# FPGA.net
KiCad netlist of a schematic drawn in Altium Designer
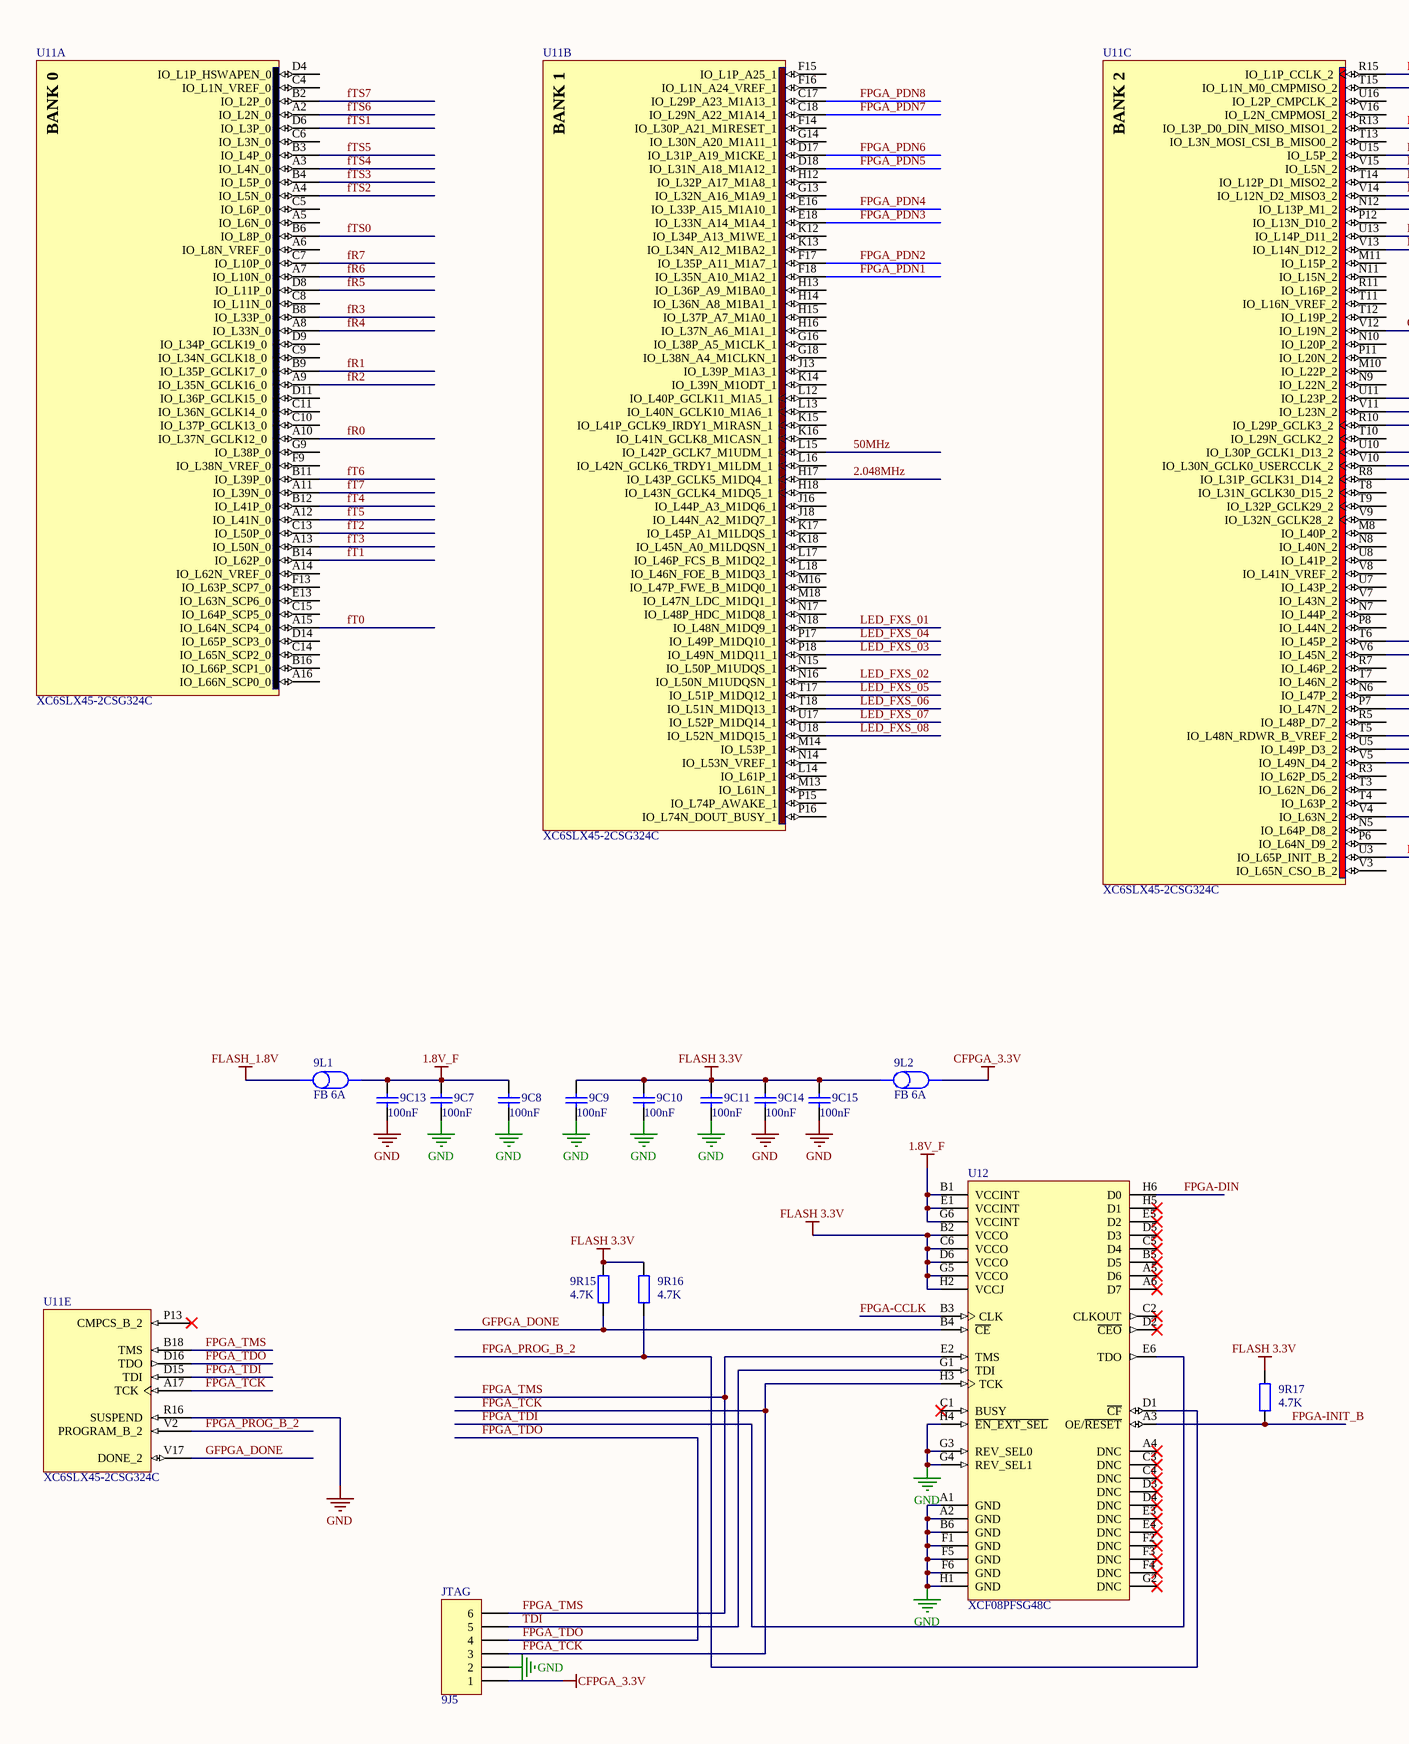
[diagram p0: FPGA.SchDoc, left]
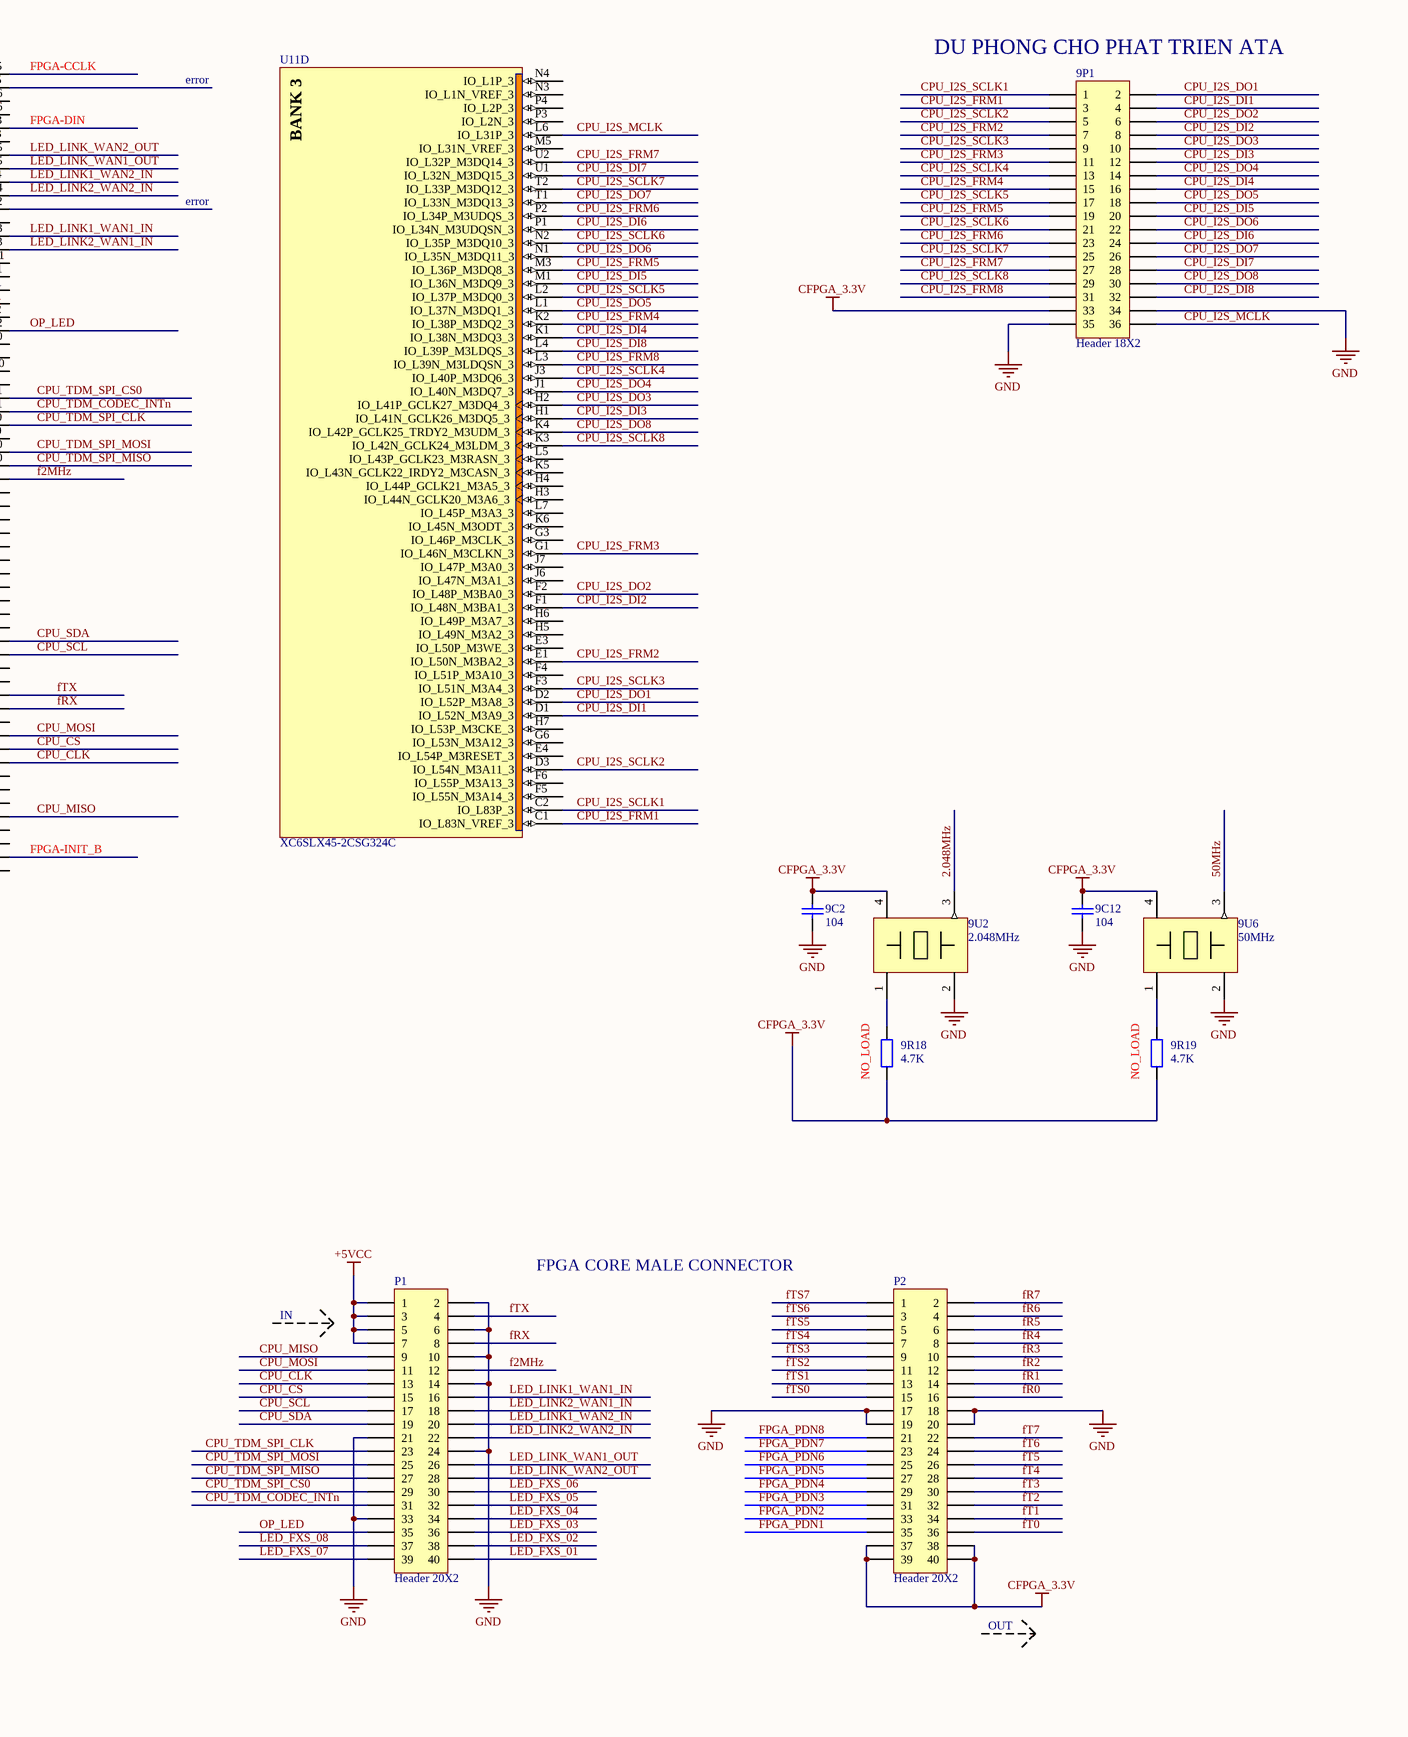
[diagram p1: FPGA.SchDoc, right]

(export (version "E")
  (design (tool "Eeschema 10.0.6"))
  (components
    (comp (ref "9C2")
      (value "CAP1")
      (footprint "0805C")
      (fields (field (name "CAP") "104"))
      (libsource (lib "BANGGOC") (part "CAP1"))
    )
    (comp (ref "9C7")
      (value "100nF")
      (footprint "C0402")
      (description "CAP CER 10V 10% 0402")
      (libsource (lib "my_lib") (part "CAP"))
    )
    (comp (ref "9C8")
      (value "100nF")
      (footprint "C0402")
      (description "CAP CER 10V 10% 0402")
      (libsource (lib "my_lib") (part "CAP"))
    )
    (comp (ref "9C9")
      (value "100nF")
      (footprint "C0402")
      (description "CAP CER 10V 10% 0402")
      (libsource (lib "my_lib") (part "CAP"))
    )
    (comp (ref "9C10")
      (value "100nF")
      (footprint "C0402")
      (description "CAP CER 10V 10% 0402")
      (libsource (lib "my_lib") (part "CAP"))
    )
    (comp (ref "9C11")
      (value "100nF")
      (footprint "C0402")
      (description "CAP CER 10V 10% 0402")
      (libsource (lib "my_lib") (part "CAP"))
    )
    (comp (ref "9C12")
      (value "CAP1")
      (footprint "0805C")
      (fields (field (name "CAP") "104"))
      (libsource (lib "BANGGOC") (part "CAP1"))
    )
    (comp (ref "9C13")
      (value "100nF")
      (footprint "C0402")
      (description "CAP CER 10V 10% 0402")
      (libsource (lib "my_lib") (part "CAP"))
    )
    (comp (ref "9C14")
      (value "100nF")
      (footprint "C0402")
      (description "CAP CER 10V 10% 0402")
      (libsource (lib "my_lib") (part "CAP"))
    )
    (comp (ref "9C15")
      (value "100nF")
      (footprint "C0402")
      (description "CAP CER 10V 10% 0402")
      (libsource (lib "my_lib") (part "CAP"))
    )
    (comp (ref "9J5")
      (value "JTAG")
      (footprint "HDR 1X6")
      (description "CONNECTOR HEADER 1x6 PITCH 2.54")
      (libsource (lib "my_lib") (part "J6x1"))
    )
    (comp (ref "9L1")
      (value "FB 6A")
      (footprint "0805")
      (description "FERRITE BEAD 22 OHM 0805 1LN")
      (fields (field (name "PART_NUMBER") "BLM21PG220SN1D"))
      (libsource (lib "HONG") (part "FB"))
    )
    (comp (ref "9L2")
      (value "FB 6A")
      (footprint "0805")
      (description "FERRITE BEAD 22 OHM 0805 1LN")
      (fields (field (name "PART_NUMBER") "BLM21PG220SN1D"))
      (libsource (lib "HONG") (part "FB"))
    )
    (comp (ref "9P1")
      (value "Header 18X2")
      (footprint "HDR2X18")
      (description "Header, 18-Pin, Dual row")
      (fields (field (name "PUBLISHER") "Altium Limited"))
      (libsource (lib "Miscellaneous Connectors") (part "Header 18X2"))
    )
    (comp (ref "9R15")
      (value "4.7K")
      (footprint "0603_1")
      (description "RES 1/8W 5% 0603")
      (libsource (lib "my_lib") (part "RES"))
    )
    (comp (ref "9R16")
      (value "4.7K")
      (footprint "0603_1")
      (description "RES 1/8W 5% 0603")
      (libsource (lib "my_lib") (part "RES"))
    )
    (comp (ref "9R17")
      (value "4.7K")
      (footprint "0603_1")
      (description "RES 1/8W 5% 0603")
      (libsource (lib "my_lib") (part "RES"))
    )
    (comp (ref "9R18")
      (value "4.7K")
      (footprint "0603_1")
      (description "RES 1/8W 5% 0603")
      (fields (field (name "LOAD") "NO_LOAD"))
      (libsource (lib "my_lib") (part "RES"))
    )
    (comp (ref "9R19")
      (value "4.7K")
      (footprint "0603_1")
      (description "RES 1/8W 5% 0603")
      (fields (field (name "LOAD") "NO_LOAD"))
      (libsource (lib "my_lib") (part "RES"))
    )
    (comp (ref "9U2")
      (value "2.048MHz")
      (footprint "CB3LV-3I-2M0480")
      (libsource (lib "BANGGOC") (part "CRYSTAL2"))
    )
    (comp (ref "9U6")
      (value "50MHz")
      (footprint "CB3LV-3I-2M0480")
      (libsource (lib "BANGGOC") (part "CRYSTAL2"))
    )
    (comp (ref "P1")
      (value "Header 20X2")
      (footprint "HEADER 40P MALE")
      (description "Header, 20-Pin, Dual row")
      (fields (field (name "PUBLISHER") "Altium Limited"))
      (libsource (lib "Miscellaneous Connectors") (part "Header 20X2"))
    )
    (comp (ref "P2")
      (value "Header 20X2")
      (footprint "HEADER 40P MALE")
      (description "Header, 20-Pin, Dual row")
      (fields (field (name "PUBLISHER") "Altium Limited"))
      (libsource (lib "Miscellaneous Connectors") (part "Header 20X2"))
    )
    (comp (ref "U11")
      (value "XC6SLX45-2CSG324C")
      (footprint "CSG324")
      (fields (field (name "PUBLISHER") "Altium Limited"))
      (libsource (lib "") (part "XC6SLX45-2CSG324C_1"))
    )
    (comp (ref "U12")
      (value "XCF08PFSG48C")
      (footprint "XCF08PFSG48C")
      (fields (field (name "PUBLISHER") "Altium Limited"))
      (libsource (lib "my_lib") (part "XCF08PFSG48C"))
    )
  )
  (nets
    (net (code "1") (name "+5VCC") (class "Default")
      (node (ref "P1") (pin "1") (pinfunction "1_1") (pintype "passive"))
      (node (ref "P1") (pin "3") (pinfunction "3_3") (pintype "passive"))
      (node (ref "P1") (pin "5") (pinfunction "5_5") (pintype "passive"))
      (node (ref "P1") (pin "7") (pinfunction "7_7") (pintype "passive"))
    )
    (net (code "2") (name "/2.048MHz") (class "Default")
      (node (ref "9U2") (pin "3") (pinfunction "3_3") (pintype "output"))
      (node (ref "U11") (pin "H17") (pinfunction "IO_L43P_GCLK5_M1DQ4_1_H17") (pintype "bidirectional"))
    )
    (net (code "3") (name "/50MHz") (class "Default")
      (node (ref "9U6") (pin "3") (pinfunction "3_3") (pintype "output"))
      (node (ref "U11") (pin "L15") (pinfunction "IO_L42P_GCLK7_M1UDM_1_L15") (pintype "bidirectional"))
    )
    (net (code "4") (name "/CPU_CLK") (class "Default")
      (node (ref "P1") (pin "13") (pinfunction "13_13") (pintype "passive"))
      (node (ref "U11") (pin "V5") (pinfunction "IO_L49N_D4_2_V5") (pintype "bidirectional"))
    )
    (net (code "5") (name "/CPU_CS") (class "Default")
      (node (ref "P1") (pin "15") (pinfunction "15_15") (pintype "passive"))
      (node (ref "U11") (pin "U5") (pinfunction "IO_L49P_D3_2_U5") (pintype "bidirectional"))
    )
    (net (code "6") (name "/CPU_I2S_DI1") (class "Default")
      (node (ref "9P1") (pin "4") (pinfunction "4_4") (pintype "passive"))
      (node (ref "U11") (pin "D1") (pinfunction "IO_L52N_M3A9_3_D1") (pintype "bidirectional"))
    )
    (net (code "7") (name "/CPU_I2S_DI2") (class "Default")
      (node (ref "9P1") (pin "8") (pinfunction "8_8") (pintype "passive"))
      (node (ref "U11") (pin "F1") (pinfunction "IO_L48N_M3BA1_3_F1") (pintype "bidirectional"))
    )
    (net (code "8") (name "/CPU_I2S_DI3") (class "Default")
      (node (ref "9P1") (pin "12") (pinfunction "12_12") (pintype "passive"))
      (node (ref "U11") (pin "H1") (pinfunction "IO_L41N_GCLK26_M3DQ5_3_H1") (pintype "bidirectional"))
    )
    (net (code "9") (name "/CPU_I2S_DI4") (class "Default")
      (node (ref "9P1") (pin "16") (pinfunction "16_16") (pintype "passive"))
      (node (ref "U11") (pin "K1") (pinfunction "IO_L38N_M3DQ3_3_K1") (pintype "bidirectional"))
    )
    (net (code "10") (name "/CPU_I2S_DI5") (class "Default")
      (node (ref "9P1") (pin "20") (pinfunction "20_20") (pintype "passive"))
      (node (ref "U11") (pin "M1") (pinfunction "IO_L36N_M3DQ9_3_M1") (pintype "bidirectional"))
    )
    (net (code "11") (name "/CPU_I2S_DI6") (class "Default")
      (node (ref "9P1") (pin "24") (pinfunction "24_24") (pintype "passive"))
      (node (ref "U11") (pin "P1") (pinfunction "IO_L34N_M3UDQSN_3_P1") (pintype "bidirectional"))
    )
    (net (code "12") (name "/CPU_I2S_DI7") (class "Default")
      (node (ref "9P1") (pin "28") (pinfunction "28_28") (pintype "passive"))
      (node (ref "U11") (pin "U1") (pinfunction "IO_L32N_M3DQ15_3_U1") (pintype "bidirectional"))
    )
    (net (code "13") (name "/CPU_I2S_DI8") (class "Default")
      (node (ref "9P1") (pin "32") (pinfunction "32_32") (pintype "passive"))
      (node (ref "U11") (pin "L4") (pinfunction "IO_L39P_M3LDQS_3_L4") (pintype "bidirectional"))
    )
    (net (code "14") (name "/CPU_I2S_DO1") (class "Default")
      (node (ref "9P1") (pin "2") (pinfunction "2_2") (pintype "passive"))
      (node (ref "U11") (pin "D2") (pinfunction "IO_L52P_M3A8_3_D2") (pintype "bidirectional"))
    )
    (net (code "15") (name "/CPU_I2S_DO2") (class "Default")
      (node (ref "9P1") (pin "6") (pinfunction "6_6") (pintype "passive"))
      (node (ref "U11") (pin "F2") (pinfunction "IO_L48P_M3BA0_3_F2") (pintype "bidirectional"))
    )
    (net (code "16") (name "/CPU_I2S_DO3") (class "Default")
      (node (ref "9P1") (pin "10") (pinfunction "10_10") (pintype "passive"))
      (node (ref "U11") (pin "H2") (pinfunction "IO_L41P_GCLK27_M3DQ4_3_H2") (pintype "bidirectional"))
    )
    (net (code "17") (name "/CPU_I2S_DO4") (class "Default")
      (node (ref "9P1") (pin "14") (pinfunction "14_14") (pintype "passive"))
      (node (ref "U11") (pin "J1") (pinfunction "IO_L40N_M3DQ7_3_J1") (pintype "bidirectional"))
    )
    (net (code "18") (name "/CPU_I2S_DO5") (class "Default")
      (node (ref "9P1") (pin "18") (pinfunction "18_18") (pintype "passive"))
      (node (ref "U11") (pin "L1") (pinfunction "IO_L37N_M3DQ1_3_L1") (pintype "bidirectional"))
    )
    (net (code "19") (name "/CPU_I2S_DO6") (class "Default")
      (node (ref "9P1") (pin "22") (pinfunction "22_22") (pintype "passive"))
      (node (ref "U11") (pin "N1") (pinfunction "IO_L35N_M3DQ11_3_N1") (pintype "bidirectional"))
    )
    (net (code "20") (name "/CPU_I2S_DO7") (class "Default")
      (node (ref "9P1") (pin "26") (pinfunction "26_26") (pintype "passive"))
      (node (ref "U11") (pin "T1") (pinfunction "IO_L33N_M3DQ13_3_T1") (pintype "bidirectional"))
    )
    (net (code "21") (name "/CPU_I2S_DO8") (class "Default")
      (node (ref "9P1") (pin "30") (pinfunction "30_30") (pintype "passive"))
      (node (ref "U11") (pin "K4") (pinfunction "IO_L42P_GCLK25_TRDY2_M3UDM_3_K4") (pintype "bidirectional"))
    )
    (net (code "22") (name "/CPU_I2S_FRM1") (class "Default")
      (node (ref "9P1") (pin "3") (pinfunction "3_3") (pintype "passive"))
      (node (ref "U11") (pin "C1") (pinfunction "IO_L83N_VREF_3_C1") (pintype "bidirectional"))
    )
    (net (code "23") (name "/CPU_I2S_FRM2") (class "Default")
      (node (ref "9P1") (pin "7") (pinfunction "7_7") (pintype "passive"))
      (node (ref "U11") (pin "E1") (pinfunction "IO_L50N_M3BA2_3_E1") (pintype "bidirectional"))
    )
    (net (code "24") (name "/CPU_I2S_FRM3") (class "Default")
      (node (ref "9P1") (pin "11") (pinfunction "11_11") (pintype "passive"))
      (node (ref "U11") (pin "G1") (pinfunction "IO_L46N_M3CLKN_3_G1") (pintype "bidirectional"))
    )
    (net (code "25") (name "/CPU_I2S_FRM4") (class "Default")
      (node (ref "9P1") (pin "15") (pinfunction "15_15") (pintype "passive"))
      (node (ref "U11") (pin "K2") (pinfunction "IO_L38P_M3DQ2_3_K2") (pintype "bidirectional"))
    )
    (net (code "26") (name "/CPU_I2S_FRM5") (class "Default")
      (node (ref "9P1") (pin "19") (pinfunction "19_19") (pintype "passive"))
      (node (ref "U11") (pin "M3") (pinfunction "IO_L36P_M3DQ8_3_M3") (pintype "bidirectional"))
    )
    (net (code "27") (name "/CPU_I2S_FRM6") (class "Default")
      (node (ref "9P1") (pin "23") (pinfunction "23_23") (pintype "passive"))
      (node (ref "U11") (pin "P2") (pinfunction "IO_L34P_M3UDQS_3_P2") (pintype "bidirectional"))
    )
    (net (code "28") (name "/CPU_I2S_FRM7") (class "Default")
      (node (ref "9P1") (pin "27") (pinfunction "27_27") (pintype "passive"))
      (node (ref "U11") (pin "U2") (pinfunction "IO_L32P_M3DQ14_3_U2") (pintype "bidirectional"))
    )
    (net (code "29") (name "/CPU_I2S_FRM8") (class "Default")
      (node (ref "9P1") (pin "31") (pinfunction "31_31") (pintype "passive"))
      (node (ref "U11") (pin "L3") (pinfunction "IO_L39N_M3LDQSN_3_L3") (pintype "bidirectional"))
    )
    (net (code "30") (name "/CPU_I2S_MCLK") (class "Default")
      (node (ref "9P1") (pin "36") (pinfunction "36_36") (pintype "passive"))
      (node (ref "U11") (pin "L6") (pinfunction "IO_L31P_3_L6") (pintype "bidirectional"))
    )
    (net (code "31") (name "/CPU_I2S_SCLK1") (class "Default")
      (node (ref "9P1") (pin "1") (pinfunction "1_1") (pintype "passive"))
      (node (ref "U11") (pin "C2") (pinfunction "IO_L83P_3_C2") (pintype "bidirectional"))
    )
    (net (code "32") (name "/CPU_I2S_SCLK2") (class "Default")
      (node (ref "9P1") (pin "5") (pinfunction "5_5") (pintype "passive"))
      (node (ref "U11") (pin "D3") (pinfunction "IO_L54N_M3A11_3_D3") (pintype "bidirectional"))
    )
    (net (code "33") (name "/CPU_I2S_SCLK3") (class "Default")
      (node (ref "9P1") (pin "9") (pinfunction "9_9") (pintype "passive"))
      (node (ref "U11") (pin "F3") (pinfunction "IO_L51N_M3A4_3_F3") (pintype "bidirectional"))
    )
    (net (code "34") (name "/CPU_I2S_SCLK4") (class "Default")
      (node (ref "9P1") (pin "13") (pinfunction "13_13") (pintype "passive"))
      (node (ref "U11") (pin "J3") (pinfunction "IO_L40P_M3DQ6_3_J3") (pintype "bidirectional"))
    )
    (net (code "35") (name "/CPU_I2S_SCLK5") (class "Default")
      (node (ref "9P1") (pin "17") (pinfunction "17_17") (pintype "passive"))
      (node (ref "U11") (pin "L2") (pinfunction "IO_L37P_M3DQ0_3_L2") (pintype "bidirectional"))
    )
    (net (code "36") (name "/CPU_I2S_SCLK6") (class "Default")
      (node (ref "9P1") (pin "21") (pinfunction "21_21") (pintype "passive"))
      (node (ref "U11") (pin "N2") (pinfunction "IO_L35P_M3DQ10_3_N2") (pintype "bidirectional"))
    )
    (net (code "37") (name "/CPU_I2S_SCLK7") (class "Default")
      (node (ref "9P1") (pin "25") (pinfunction "25_25") (pintype "passive"))
      (node (ref "U11") (pin "T2") (pinfunction "IO_L33P_M3DQ12_3_T2") (pintype "bidirectional"))
    )
    (net (code "38") (name "/CPU_I2S_SCLK8") (class "Default")
      (node (ref "9P1") (pin "29") (pinfunction "29_29") (pintype "passive"))
      (node (ref "U11") (pin "K3") (pinfunction "IO_L42N_GCLK24_M3LDM_3_K3") (pintype "bidirectional"))
    )
    (net (code "39") (name "/CPU_MISO") (class "Default")
      (node (ref "P1") (pin "9") (pinfunction "9_9") (pintype "passive"))
      (node (ref "U11") (pin "V4") (pinfunction "IO_L63N_2_V4") (pintype "bidirectional"))
    )
    (net (code "40") (name "/CPU_MOSI") (class "Default")
      (node (ref "P1") (pin "11") (pinfunction "11_11") (pintype "passive"))
      (node (ref "U11") (pin "T5") (pinfunction "IO_L48N_RDWR_B_VREF_2_T5") (pintype "bidirectional"))
    )
    (net (code "41") (name "/CPU_SCL") (class "Default")
      (node (ref "P1") (pin "17") (pinfunction "17_17") (pintype "passive"))
      (node (ref "U11") (pin "V6") (pinfunction "IO_L45N_2_V6") (pintype "bidirectional"))
    )
    (net (code "42") (name "/CPU_SDA") (class "Default")
      (node (ref "P1") (pin "19") (pinfunction "19_19") (pintype "passive"))
      (node (ref "U11") (pin "T6") (pinfunction "IO_L45P_2_T6") (pintype "bidirectional"))
    )
    (net (code "43") (name "/CPU_TDM_CODEC_INTn") (class "Default")
      (node (ref "P1") (pin "31") (pinfunction "31_31") (pintype "passive"))
      (node (ref "U11") (pin "V11") (pinfunction "IO_L23N_2_V11") (pintype "bidirectional"))
    )
    (net (code "44") (name "/CPU_TDM_SPI_CLK") (class "Default")
      (node (ref "P1") (pin "23") (pinfunction "23_23") (pintype "passive"))
      (node (ref "U11") (pin "R10") (pinfunction "IO_L29P_GCLK3_2_R10") (pintype "bidirectional"))
    )
    (net (code "45") (name "/CPU_TDM_SPI_CS0") (class "Default")
      (node (ref "P1") (pin "29") (pinfunction "29_29") (pintype "passive"))
      (node (ref "U11") (pin "U11") (pinfunction "IO_L23P_2_U11") (pintype "bidirectional"))
    )
    (net (code "46") (name "/CPU_TDM_SPI_MISO") (class "Default")
      (node (ref "P1") (pin "27") (pinfunction "27_27") (pintype "passive"))
      (node (ref "U11") (pin "V10") (pinfunction "IO_L30N_GCLK0_USERCCLK_2_V10") (pintype "bidirectional"))
    )
    (net (code "47") (name "/CPU_TDM_SPI_MOSI") (class "Default")
      (node (ref "P1") (pin "25") (pinfunction "25_25") (pintype "passive"))
      (node (ref "U11") (pin "U10") (pinfunction "IO_L30P_GCLK1_D13_2_U10") (pintype "bidirectional"))
    )
    (net (code "48") (name "/FPGA-CCLK") (class "Default")
      (node (ref "U11") (pin "R15") (pinfunction "IO_L1P_CCLK_2_R15") (pintype "bidirectional"))
      (node (ref "U12") (pin "B3") (pinfunction "CLK_B3") (pintype "input"))
    )
    (net (code "49") (name "/FPGA-DIN") (class "Default")
      (node (ref "U11") (pin "R13") (pinfunction "IO_L3P_D0_DIN_MISO_MISO1_2_R13") (pintype "bidirectional"))
      (node (ref "U12") (pin "H6") (pinfunction "D0_H6") (pintype "tri_state"))
    )
    (net (code "50") (name "/FPGA-INIT_B") (class "Default")
      (node (ref "9R17") (pin "1") (pinfunction "1_1") (pintype "passive"))
      (node (ref "U11") (pin "U3") (pinfunction "IO_L65P_INIT_B_2_U3") (pintype "bidirectional"))
      (node (ref "U12") (pin "A3") (pinfunction "OE/~{RESET}_A3") (pintype "bidirectional"))
    )
    (net (code "51") (name "/FPGA_PDN1") (class "Default")
      (node (ref "P2") (pin "35") (pinfunction "35_35") (pintype "passive"))
      (node (ref "U11") (pin "F18") (pinfunction "IO_L35N_A10_M1A2_1_F18") (pintype "bidirectional"))
    )
    (net (code "52") (name "/FPGA_PDN2") (class "Default")
      (node (ref "P2") (pin "33") (pinfunction "33_33") (pintype "passive"))
      (node (ref "U11") (pin "F17") (pinfunction "IO_L35P_A11_M1A7_1_F17") (pintype "bidirectional"))
    )
    (net (code "53") (name "/FPGA_PDN3") (class "Default")
      (node (ref "P2") (pin "31") (pinfunction "31_31") (pintype "passive"))
      (node (ref "U11") (pin "E18") (pinfunction "IO_L33N_A14_M1A4_1_E18") (pintype "bidirectional"))
    )
    (net (code "54") (name "/FPGA_PDN4") (class "Default")
      (node (ref "P2") (pin "29") (pinfunction "29_29") (pintype "passive"))
      (node (ref "U11") (pin "E16") (pinfunction "IO_L33P_A15_M1A10_1_E16") (pintype "bidirectional"))
    )
    (net (code "55") (name "/FPGA_PDN5") (class "Default")
      (node (ref "P2") (pin "27") (pinfunction "27_27") (pintype "passive"))
      (node (ref "U11") (pin "D18") (pinfunction "IO_L31N_A18_M1A12_1_D18") (pintype "bidirectional"))
    )
    (net (code "56") (name "/FPGA_PDN6") (class "Default")
      (node (ref "P2") (pin "25") (pinfunction "25_25") (pintype "passive"))
      (node (ref "U11") (pin "D17") (pinfunction "IO_L31P_A19_M1CKE_1_D17") (pintype "bidirectional"))
    )
    (net (code "57") (name "/FPGA_PDN7") (class "Default")
      (node (ref "P2") (pin "23") (pinfunction "23_23") (pintype "passive"))
      (node (ref "U11") (pin "C18") (pinfunction "IO_L29N_A22_M1A14_1_C18") (pintype "bidirectional"))
    )
    (net (code "58") (name "/FPGA_PDN8") (class "Default")
      (node (ref "P2") (pin "21") (pinfunction "21_21") (pintype "passive"))
      (node (ref "U11") (pin "C17") (pinfunction "IO_L29P_A23_M1A13_1_C17") (pintype "bidirectional"))
    )
    (net (code "59") (name "/FPGA_PROG_B_2") (class "Default")
      (node (ref "9R16") (pin "1") (pinfunction "1_1") (pintype "passive"))
      (node (ref "U11") (pin "V2") (pinfunction "PROGRAM_B_2_V2") (pintype "input"))
      (node (ref "U12") (pin "D1") (pinfunction "~{CF}_D1") (pintype "bidirectional"))
    )
    (net (code "60") (name "/FPGA_TCK") (class "Default")
      (node (ref "9J5") (pin "3") (pinfunction "3_3") (pintype "passive"))
      (node (ref "U11") (pin "A17") (pinfunction "TCK_A17") (pintype "input"))
      (node (ref "U12") (pin "H3") (pinfunction "TCK_H3") (pintype "input"))
    )
    (net (code "61") (name "/FPGA_TDI") (class "Default")
      (node (ref "U11") (pin "D15") (pinfunction "TDI_D15") (pintype "input"))
      (node (ref "U12") (pin "E6") (pinfunction "TDO_E6") (pintype "output"))
    )
    (net (code "62") (name "/FPGA_TDO") (class "Default")
      (node (ref "9J5") (pin "4") (pinfunction "4_4") (pintype "passive"))
      (node (ref "U11") (pin "D16") (pinfunction "TDO_D16") (pintype "output"))
    )
    (net (code "63") (name "/FPGA_TMS") (class "Default")
      (node (ref "9J5") (pin "6") (pinfunction "6_6") (pintype "passive"))
      (node (ref "U11") (pin "B18") (pinfunction "TMS_B18") (pintype "input"))
      (node (ref "U12") (pin "E2") (pinfunction "TMS_E2") (pintype "input"))
    )
    (net (code "64") (name "/GFPGA_DONE") (class "Default")
      (node (ref "9R15") (pin "1") (pinfunction "1_1") (pintype "passive"))
      (node (ref "U11") (pin "V17") (pinfunction "DONE_2_V17") (pintype "bidirectional"))
      (node (ref "U12") (pin "B4") (pinfunction "~{CE}_B4") (pintype "input"))
    )
    (net (code "65") (name "/LED_FXS_01") (class "Default")
      (node (ref "P1") (pin "40") (pinfunction "40_40") (pintype "passive"))
      (node (ref "U11") (pin "N18") (pinfunction "IO_L48N_M1DQ9_1_N18") (pintype "bidirectional"))
    )
    (net (code "66") (name "/LED_FXS_02") (class "Default")
      (node (ref "P1") (pin "38") (pinfunction "38_38") (pintype "passive"))
      (node (ref "U11") (pin "N16") (pinfunction "IO_L50N_M1UDQSN_1_N16") (pintype "bidirectional"))
    )
    (net (code "67") (name "/LED_FXS_03") (class "Default")
      (node (ref "P1") (pin "36") (pinfunction "36_36") (pintype "passive"))
      (node (ref "U11") (pin "P18") (pinfunction "IO_L49N_M1DQ11_1_P18") (pintype "bidirectional"))
    )
    (net (code "68") (name "/LED_FXS_04") (class "Default")
      (node (ref "P1") (pin "34") (pinfunction "34_34") (pintype "passive"))
      (node (ref "U11") (pin "P17") (pinfunction "IO_L49P_M1DQ10_1_P17") (pintype "bidirectional"))
    )
    (net (code "69") (name "/LED_FXS_05") (class "Default")
      (node (ref "P1") (pin "32") (pinfunction "32_32") (pintype "passive"))
      (node (ref "U11") (pin "T17") (pinfunction "IO_L51P_M1DQ12_1_T17") (pintype "bidirectional"))
    )
    (net (code "70") (name "/LED_FXS_06") (class "Default")
      (node (ref "P1") (pin "30") (pinfunction "30_30") (pintype "passive"))
      (node (ref "U11") (pin "T18") (pinfunction "IO_L51N_M1DQ13_1_T18") (pintype "bidirectional"))
    )
    (net (code "71") (name "/LED_FXS_07") (class "Default")
      (node (ref "P1") (pin "39") (pinfunction "39_39") (pintype "passive"))
      (node (ref "U11") (pin "U17") (pinfunction "IO_L52P_M1DQ14_1_U17") (pintype "bidirectional"))
    )
    (net (code "72") (name "/LED_FXS_08") (class "Default")
      (node (ref "P1") (pin "37") (pinfunction "37_37") (pintype "passive"))
      (node (ref "U11") (pin "U18") (pinfunction "IO_L52N_M1DQ15_1_U18") (pintype "bidirectional"))
    )
    (net (code "73") (name "/LED_LINK1_WAN1_IN") (class "Default")
      (node (ref "P1") (pin "16") (pinfunction "16_16") (pintype "passive"))
      (node (ref "U11") (pin "U13") (pinfunction "IO_L14P_D11_2_U13") (pintype "bidirectional"))
    )
    (net (code "74") (name "/LED_LINK1_WAN2_IN") (class "Default")
      (node (ref "P1") (pin "20") (pinfunction "20_20") (pintype "passive"))
      (node (ref "U11") (pin "T14") (pinfunction "IO_L12P_D1_MISO2_2_T14") (pintype "bidirectional"))
    )
    (net (code "75") (name "/LED_LINK2_WAN1_IN") (class "Default")
      (node (ref "P1") (pin "18") (pinfunction "18_18") (pintype "passive"))
      (node (ref "U11") (pin "V13") (pinfunction "IO_L14N_D12_2_V13") (pintype "bidirectional"))
    )
    (net (code "76") (name "/LED_LINK2_WAN2_IN") (class "Default")
      (node (ref "P1") (pin "22") (pinfunction "22_22") (pintype "passive"))
      (node (ref "U11") (pin "V14") (pinfunction "IO_L12N_D2_MISO3_2_V14") (pintype "bidirectional"))
    )
    (net (code "77") (name "/LED_LINK_WAN1_OUT") (class "Default")
      (node (ref "P1") (pin "26") (pinfunction "26_26") (pintype "passive"))
      (node (ref "U11") (pin "V15") (pinfunction "IO_L5N_2_V15") (pintype "bidirectional"))
    )
    (net (code "78") (name "/LED_LINK_WAN2_OUT") (class "Default")
      (node (ref "P1") (pin "28") (pinfunction "28_28") (pintype "passive"))
      (node (ref "U11") (pin "U15") (pinfunction "IO_L5P_2_U15") (pintype "bidirectional"))
    )
    (net (code "79") (name "/OP_LED") (class "Default")
      (node (ref "P1") (pin "35") (pinfunction "35_35") (pintype "passive"))
      (node (ref "U11") (pin "V12") (pinfunction "IO_L19N_2_V12") (pintype "bidirectional"))
    )
    (net (code "80") (name "/TDI") (class "Default")
      (node (ref "9J5") (pin "5") (pinfunction "5_5") (pintype "passive"))
      (node (ref "U12") (pin "G1") (pinfunction "TDI_G1") (pintype "input"))
    )
    (net (code "81") (name "/f2MHz") (class "Default")
      (node (ref "P1") (pin "12") (pinfunction "12_12") (pintype "passive"))
      (node (ref "U11") (pin "R8") (pinfunction "IO_L31P_GCLK31_D14_2_R8") (pintype "bidirectional"))
    )
    (net (code "82") (name "/fR0") (class "Default")
      (node (ref "P2") (pin "16") (pinfunction "16_16") (pintype "passive"))
      (node (ref "U11") (pin "A10") (pinfunction "IO_L37N_GCLK12_0_A10") (pintype "bidirectional"))
    )
    (net (code "83") (name "/fR1") (class "Default")
      (node (ref "P2") (pin "14") (pinfunction "14_14") (pintype "passive"))
      (node (ref "U11") (pin "B9") (pinfunction "IO_L35P_GCLK17_0_B9") (pintype "bidirectional"))
    )
    (net (code "84") (name "/fR2") (class "Default")
      (node (ref "P2") (pin "12") (pinfunction "12_12") (pintype "passive"))
      (node (ref "U11") (pin "A9") (pinfunction "IO_L35N_GCLK16_0_A9") (pintype "bidirectional"))
    )
    (net (code "85") (name "/fR3") (class "Default")
      (node (ref "P2") (pin "10") (pinfunction "10_10") (pintype "passive"))
      (node (ref "U11") (pin "B8") (pinfunction "IO_L33P_0_B8") (pintype "bidirectional"))
    )
    (net (code "86") (name "/fR4") (class "Default")
      (node (ref "P2") (pin "8") (pinfunction "8_8") (pintype "passive"))
      (node (ref "U11") (pin "A8") (pinfunction "IO_L33N_0_A8") (pintype "bidirectional"))
    )
    (net (code "87") (name "/fR5") (class "Default")
      (node (ref "P2") (pin "6") (pinfunction "6_6") (pintype "passive"))
      (node (ref "U11") (pin "D8") (pinfunction "IO_L11P_0_D8") (pintype "bidirectional"))
    )
    (net (code "88") (name "/fR6") (class "Default")
      (node (ref "P2") (pin "4") (pinfunction "4_4") (pintype "passive"))
      (node (ref "U11") (pin "A7") (pinfunction "IO_L10N_0_A7") (pintype "bidirectional"))
    )
    (net (code "89") (name "/fR7") (class "Default")
      (node (ref "P2") (pin "2") (pinfunction "2_2") (pintype "passive"))
      (node (ref "U11") (pin "C7") (pinfunction "IO_L10P_0_C7") (pintype "bidirectional"))
    )
    (net (code "90") (name "/fRX") (class "Default")
      (node (ref "P1") (pin "8") (pinfunction "8_8") (pintype "passive"))
      (node (ref "U11") (pin "P7") (pinfunction "IO_L47N_2_P7") (pintype "bidirectional"))
    )
    (net (code "91") (name "/fT0") (class "Default")
      (node (ref "P2") (pin "36") (pinfunction "36_36") (pintype "passive"))
      (node (ref "U11") (pin "A15") (pinfunction "IO_L64N_SCP4_0_A15") (pintype "bidirectional"))
    )
    (net (code "92") (name "/fT1") (class "Default")
      (node (ref "P2") (pin "34") (pinfunction "34_34") (pintype "passive"))
      (node (ref "U11") (pin "B14") (pinfunction "IO_L62P_0_B14") (pintype "bidirectional"))
    )
    (net (code "93") (name "/fT2") (class "Default")
      (node (ref "P2") (pin "32") (pinfunction "32_32") (pintype "passive"))
      (node (ref "U11") (pin "C13") (pinfunction "IO_L50P_0_C13") (pintype "bidirectional"))
    )
    (net (code "94") (name "/fT3") (class "Default")
      (node (ref "P2") (pin "30") (pinfunction "30_30") (pintype "passive"))
      (node (ref "U11") (pin "A13") (pinfunction "IO_L50N_0_A13") (pintype "bidirectional"))
    )
    (net (code "95") (name "/fT4") (class "Default")
      (node (ref "P2") (pin "28") (pinfunction "28_28") (pintype "passive"))
      (node (ref "U11") (pin "B12") (pinfunction "IO_L41P_0_B12") (pintype "bidirectional"))
    )
    (net (code "96") (name "/fT5") (class "Default")
      (node (ref "P2") (pin "26") (pinfunction "26_26") (pintype "passive"))
      (node (ref "U11") (pin "A12") (pinfunction "IO_L41N_0_A12") (pintype "bidirectional"))
    )
    (net (code "97") (name "/fT6") (class "Default")
      (node (ref "P2") (pin "24") (pinfunction "24_24") (pintype "passive"))
      (node (ref "U11") (pin "B11") (pinfunction "IO_L39P_0_B11") (pintype "bidirectional"))
    )
    (net (code "98") (name "/fT7") (class "Default")
      (node (ref "P2") (pin "22") (pinfunction "22_22") (pintype "passive"))
      (node (ref "U11") (pin "A11") (pinfunction "IO_L39N_0_A11") (pintype "bidirectional"))
    )
    (net (code "99") (name "/fTS0") (class "Default")
      (node (ref "P2") (pin "15") (pinfunction "15_15") (pintype "passive"))
      (node (ref "U11") (pin "B6") (pinfunction "IO_L8P_0_B6") (pintype "bidirectional"))
    )
    (net (code "100") (name "/fTS1") (class "Default")
      (node (ref "P2") (pin "13") (pinfunction "13_13") (pintype "passive"))
      (node (ref "U11") (pin "D6") (pinfunction "IO_L3P_0_D6") (pintype "bidirectional"))
    )
    (net (code "101") (name "/fTS2") (class "Default")
      (node (ref "P2") (pin "11") (pinfunction "11_11") (pintype "passive"))
      (node (ref "U11") (pin "A4") (pinfunction "IO_L5N_0_A4") (pintype "bidirectional"))
    )
    (net (code "102") (name "/fTS3") (class "Default")
      (node (ref "P2") (pin "9") (pinfunction "9_9") (pintype "passive"))
      (node (ref "U11") (pin "B4") (pinfunction "IO_L5P_0_B4") (pintype "bidirectional"))
    )
    (net (code "103") (name "/fTS4") (class "Default")
      (node (ref "P2") (pin "7") (pinfunction "7_7") (pintype "passive"))
      (node (ref "U11") (pin "A3") (pinfunction "IO_L4N_0_A3") (pintype "bidirectional"))
    )
    (net (code "104") (name "/fTS5") (class "Default")
      (node (ref "P2") (pin "5") (pinfunction "5_5") (pintype "passive"))
      (node (ref "U11") (pin "B3") (pinfunction "IO_L4P_0_B3") (pintype "bidirectional"))
    )
    (net (code "105") (name "/fTS6") (class "Default")
      (node (ref "P2") (pin "3") (pinfunction "3_3") (pintype "passive"))
      (node (ref "U11") (pin "A2") (pinfunction "IO_L2N_0_A2") (pintype "bidirectional"))
    )
    (net (code "106") (name "/fTS7") (class "Default")
      (node (ref "P2") (pin "1") (pinfunction "1_1") (pintype "passive"))
      (node (ref "U11") (pin "B2") (pinfunction "IO_L2P_0_B2") (pintype "bidirectional"))
    )
    (net (code "107") (name "/fTX") (class "Default")
      (node (ref "P1") (pin "4") (pinfunction "4_4") (pintype "passive"))
      (node (ref "U11") (pin "N6") (pinfunction "IO_L47P_2_N6") (pintype "bidirectional"))
    )
    (net (code "108") (name "1.8V_F") (class "Default")
      (node (ref "9C13") (pin "2") (pinfunction "2_2") (pintype "passive"))
      (node (ref "9C7") (pin "2") (pinfunction "2_2") (pintype "passive"))
      (node (ref "9C8") (pin "2") (pinfunction "2_2") (pintype "passive"))
      (node (ref "9L1") (pin "1") (pinfunction "1_1") (pintype "passive"))
      (node (ref "U12") (pin "B1") (pinfunction "VCCINT_B1") (pintype "power_in"))
      (node (ref "U12") (pin "E1") (pinfunction "VCCINT_E1") (pintype "power_in"))
      (node (ref "U12") (pin "G6") (pinfunction "VCCINT_G6") (pintype "power_in"))
    )
    (net (code "109") (name "CFPGA_3.3V") (class "Default")
      (node (ref "9C12") (pin "2") (pinfunction "2_2") (pintype "passive"))
      (node (ref "9C2") (pin "2") (pinfunction "2_2") (pintype "passive"))
      (node (ref "9J5") (pin "1") (pinfunction "1_1") (pintype "passive"))
      (node (ref "9L2") (pin "1") (pinfunction "1_1") (pintype "passive"))
      (node (ref "9P1") (pin "33") (pinfunction "33_33") (pintype "passive"))
      (node (ref "9R18") (pin "1") (pinfunction "1_1") (pintype "passive"))
      (node (ref "9R19") (pin "1") (pinfunction "1_1") (pintype "passive"))
      (node (ref "9U2") (pin "4") (pinfunction "4_4") (pintype "power_in"))
      (node (ref "9U6") (pin "4") (pinfunction "4_4") (pintype "power_in"))
      (node (ref "P2") (pin "37") (pinfunction "37_37") (pintype "passive"))
      (node (ref "P2") (pin "38") (pinfunction "38_38") (pintype "passive"))
      (node (ref "P2") (pin "39") (pinfunction "39_39") (pintype "passive"))
      (node (ref "P2") (pin "40") (pinfunction "40_40") (pintype "passive"))
    )
    (net (code "110") (name "FLASH 3.3V") (class "Default")
      (node (ref "9C10") (pin "2") (pinfunction "2_2") (pintype "passive"))
      (node (ref "9C11") (pin "2") (pinfunction "2_2") (pintype "passive"))
      (node (ref "9C14") (pin "2") (pinfunction "2_2") (pintype "passive"))
      (node (ref "9C15") (pin "2") (pinfunction "2_2") (pintype "passive"))
      (node (ref "9C9") (pin "2") (pinfunction "2_2") (pintype "passive"))
      (node (ref "9L2") (pin "2") (pinfunction "2_2") (pintype "passive"))
      (node (ref "9R15") (pin "2") (pinfunction "2_2") (pintype "passive"))
      (node (ref "9R16") (pin "2") (pinfunction "2_2") (pintype "passive"))
      (node (ref "9R17") (pin "2") (pinfunction "2_2") (pintype "passive"))
      (node (ref "U12") (pin "B2") (pinfunction "VCCO_B2") (pintype "power_in"))
      (node (ref "U12") (pin "C6") (pinfunction "VCCO_C6") (pintype "power_in"))
      (node (ref "U12") (pin "D6") (pinfunction "VCCO_D6") (pintype "power_in"))
      (node (ref "U12") (pin "G5") (pinfunction "VCCO_G5") (pintype "power_in"))
      (node (ref "U12") (pin "H2") (pinfunction "VCCJ_H2") (pintype "power_in"))
    )
    (net (code "111") (name "FLASH_1.8V") (class "Default")
      (node (ref "9L1") (pin "2") (pinfunction "2_2") (pintype "passive"))
    )
    (net (code "112") (name "GND") (class "Default")
      (node (ref "9C10") (pin "1") (pinfunction "1_1") (pintype "passive"))
      (node (ref "9C11") (pin "1") (pinfunction "1_1") (pintype "passive"))
      (node (ref "9C12") (pin "1") (pinfunction "1_1") (pintype "passive"))
      (node (ref "9C13") (pin "1") (pinfunction "1_1") (pintype "passive"))
      (node (ref "9C14") (pin "1") (pinfunction "1_1") (pintype "passive"))
      (node (ref "9C15") (pin "1") (pinfunction "1_1") (pintype "passive"))
      (node (ref "9C2") (pin "1") (pinfunction "1_1") (pintype "passive"))
      (node (ref "9C7") (pin "1") (pinfunction "1_1") (pintype "passive"))
      (node (ref "9C8") (pin "1") (pinfunction "1_1") (pintype "passive"))
      (node (ref "9C9") (pin "1") (pinfunction "1_1") (pintype "passive"))
      (node (ref "9J5") (pin "2") (pinfunction "2_2") (pintype "passive"))
      (node (ref "9P1") (pin "34") (pinfunction "34_34") (pintype "passive"))
      (node (ref "9P1") (pin "35") (pinfunction "35_35") (pintype "passive"))
      (node (ref "9U2") (pin "2") (pinfunction "2_2") (pintype "power_in"))
      (node (ref "9U6") (pin "2") (pinfunction "2_2") (pintype "power_in"))
      (node (ref "P1") (pin "10") (pinfunction "10_10") (pintype "passive"))
      (node (ref "P1") (pin "14") (pinfunction "14_14") (pintype "passive"))
      (node (ref "P1") (pin "2") (pinfunction "2_2") (pintype "passive"))
      (node (ref "P1") (pin "21") (pinfunction "21_21") (pintype "passive"))
      (node (ref "P1") (pin "24") (pinfunction "24_24") (pintype "passive"))
      (node (ref "P1") (pin "33") (pinfunction "33_33") (pintype "passive"))
      (node (ref "P1") (pin "6") (pinfunction "6_6") (pintype "passive"))
      (node (ref "P2") (pin "17") (pinfunction "17_17") (pintype "passive"))
      (node (ref "P2") (pin "18") (pinfunction "18_18") (pintype "passive"))
      (node (ref "P2") (pin "19") (pinfunction "19_19") (pintype "passive"))
      (node (ref "P2") (pin "20") (pinfunction "20_20") (pintype "passive"))
      (node (ref "U11") (pin "R16") (pinfunction "SUSPEND_R16") (pintype "input"))
      (node (ref "U12") (pin "A1") (pinfunction "GND_A1") (pintype "power_in"))
      (node (ref "U12") (pin "A2") (pinfunction "GND_A2") (pintype "power_in"))
      (node (ref "U12") (pin "B6") (pinfunction "GND_B6") (pintype "power_in"))
      (node (ref "U12") (pin "F1") (pinfunction "GND_F1") (pintype "power_in"))
      (node (ref "U12") (pin "F5") (pinfunction "GND_F5") (pintype "power_in"))
      (node (ref "U12") (pin "F6") (pinfunction "GND_F6") (pintype "power_in"))
      (node (ref "U12") (pin "G3") (pinfunction "REV_SEL0_G3") (pintype "input"))
      (node (ref "U12") (pin "G4") (pinfunction "REV_SEL1_G4") (pintype "input"))
      (node (ref "U12") (pin "H1") (pinfunction "GND_H1") (pintype "power_in"))
      (node (ref "U12") (pin "H4") (pinfunction "~{EN_EXT_SEL}_H4") (pintype "input"))
    )
    (net (code "113") (name "Net-(9R18-Pad2)") (class "Default")
      (node (ref "9R18") (pin "2") (pinfunction "2_2") (pintype "passive"))
      (node (ref "9U2") (pin "1") (pinfunction "1_1") (pintype "passive"))
    )
    (net (code "114") (name "Net-(9R19-Pad2)") (class "Default")
      (node (ref "9R19") (pin "2") (pinfunction "2_2") (pintype "passive"))
      (node (ref "9U6") (pin "1") (pinfunction "1_1") (pintype "passive"))
    )
    (net (code "115") (name "unconnected-(U11A-IO_L1N_VREF_0-PadC4)") (class "Default")
      (node (ref "U11") (pin "C4") (pinfunction "IO_L1N_VREF_0_C4") (pintype "bidirectional"))
    )
    (net (code "116") (name "unconnected-(U11A-IO_L1P_HSWAPEN_0-PadD4)") (class "Default")
      (node (ref "U11") (pin "D4") (pinfunction "IO_L1P_HSWAPEN_0_D4") (pintype "bidirectional"))
    )
    (net (code "117") (name "unconnected-(U11A-IO_L3N_0-PadC6)") (class "Default")
      (node (ref "U11") (pin "C6") (pinfunction "IO_L3N_0_C6") (pintype "bidirectional"))
    )
    (net (code "118") (name "unconnected-(U11A-IO_L6N_0-PadA5)") (class "Default")
      (node (ref "U11") (pin "A5") (pinfunction "IO_L6N_0_A5") (pintype "bidirectional"))
    )
    (net (code "119") (name "unconnected-(U11A-IO_L6P_0-PadC5)") (class "Default")
      (node (ref "U11") (pin "C5") (pinfunction "IO_L6P_0_C5") (pintype "bidirectional"))
    )
    (net (code "120") (name "unconnected-(U11A-IO_L8N_VREF_0-PadA6)") (class "Default")
      (node (ref "U11") (pin "A6") (pinfunction "IO_L8N_VREF_0_A6") (pintype "bidirectional"))
    )
    (net (code "121") (name "unconnected-(U11A-IO_L11N_0-PadC8)") (class "Default")
      (node (ref "U11") (pin "C8") (pinfunction "IO_L11N_0_C8") (pintype "bidirectional"))
    )
    (net (code "122") (name "unconnected-(U11A-IO_L34N_GCLK18_0-PadC9)") (class "Default")
      (node (ref "U11") (pin "C9") (pinfunction "IO_L34N_GCLK18_0_C9") (pintype "bidirectional"))
    )
    (net (code "123") (name "unconnected-(U11A-IO_L34P_GCLK19_0-PadD9)") (class "Default")
      (node (ref "U11") (pin "D9") (pinfunction "IO_L34P_GCLK19_0_D9") (pintype "bidirectional"))
    )
    (net (code "124") (name "unconnected-(U11A-IO_L36N_GCLK14_0-PadC11)") (class "Default")
      (node (ref "U11") (pin "C11") (pinfunction "IO_L36N_GCLK14_0_C11") (pintype "bidirectional"))
    )
    (net (code "125") (name "unconnected-(U11A-IO_L36P_GCLK15_0-PadD11)") (class "Default")
      (node (ref "U11") (pin "D11") (pinfunction "IO_L36P_GCLK15_0_D11") (pintype "bidirectional"))
    )
    (net (code "126") (name "unconnected-(U11A-IO_L37P_GCLK13_0-PadC10)") (class "Default")
      (node (ref "U11") (pin "C10") (pinfunction "IO_L37P_GCLK13_0_C10") (pintype "bidirectional"))
    )
    (net (code "127") (name "unconnected-(U11A-IO_L38N_VREF_0-PadF9)") (class "Default")
      (node (ref "U11") (pin "F9") (pinfunction "IO_L38N_VREF_0_F9") (pintype "bidirectional"))
    )
    (net (code "128") (name "unconnected-(U11A-IO_L38P_0-PadG9)") (class "Default")
      (node (ref "U11") (pin "G9") (pinfunction "IO_L38P_0_G9") (pintype "bidirectional"))
    )
    (net (code "129") (name "unconnected-(U11A-IO_L62N_VREF_0-PadA14)") (class "Default")
      (node (ref "U11") (pin "A14") (pinfunction "IO_L62N_VREF_0_A14") (pintype "bidirectional"))
    )
    (net (code "130") (name "unconnected-(U11A-IO_L63N_SCP6_0-PadE13)") (class "Default")
      (node (ref "U11") (pin "E13") (pinfunction "IO_L63N_SCP6_0_E13") (pintype "bidirectional"))
    )
    (net (code "131") (name "unconnected-(U11A-IO_L63P_SCP7_0-PadF13)") (class "Default")
      (node (ref "U11") (pin "F13") (pinfunction "IO_L63P_SCP7_0_F13") (pintype "bidirectional"))
    )
    (net (code "132") (name "unconnected-(U11A-IO_L64P_SCP5_0-PadC15)") (class "Default")
      (node (ref "U11") (pin "C15") (pinfunction "IO_L64P_SCP5_0_C15") (pintype "bidirectional"))
    )
    (net (code "133") (name "unconnected-(U11A-IO_L65N_SCP2_0-PadC14)") (class "Default")
      (node (ref "U11") (pin "C14") (pinfunction "IO_L65N_SCP2_0_C14") (pintype "bidirectional"))
    )
    (net (code "134") (name "unconnected-(U11A-IO_L65P_SCP3_0-PadD14)") (class "Default")
      (node (ref "U11") (pin "D14") (pinfunction "IO_L65P_SCP3_0_D14") (pintype "bidirectional"))
    )
    (net (code "135") (name "unconnected-(U11A-IO_L66N_SCP0_0-PadA16)") (class "Default")
      (node (ref "U11") (pin "A16") (pinfunction "IO_L66N_SCP0_0_A16") (pintype "bidirectional"))
    )
    (net (code "136") (name "unconnected-(U11A-IO_L66P_SCP1_0-PadB16)") (class "Default")
      (node (ref "U11") (pin "B16") (pinfunction "IO_L66P_SCP1_0_B16") (pintype "bidirectional"))
    )
    (net (code "137") (name "unconnected-(U11B-IO_L1N_A24_VREF_1-PadF16)") (class "Default")
      (node (ref "U11") (pin "F16") (pinfunction "IO_L1N_A24_VREF_1_F16") (pintype "bidirectional"))
    )
    (net (code "138") (name "unconnected-(U11B-IO_L1P_A25_1-PadF15)") (class "Default")
      (node (ref "U11") (pin "F15") (pinfunction "IO_L1P_A25_1_F15") (pintype "bidirectional"))
    )
    (net (code "139") (name "unconnected-(U11B-IO_L30N_A20_M1A11_1-PadG14)") (class "Default")
      (node (ref "U11") (pin "G14") (pinfunction "IO_L30N_A20_M1A11_1_G14") (pintype "bidirectional"))
    )
    (net (code "140") (name "unconnected-(U11B-IO_L30P_A21_M1RESET_1-PadF14)") (class "Default")
      (node (ref "U11") (pin "F14") (pinfunction "IO_L30P_A21_M1RESET_1_F14") (pintype "bidirectional"))
    )
    (net (code "141") (name "unconnected-(U11B-IO_L32N_A16_M1A9_1-PadG13)") (class "Default")
      (node (ref "U11") (pin "G13") (pinfunction "IO_L32N_A16_M1A9_1_G13") (pintype "bidirectional"))
    )
    (net (code "142") (name "unconnected-(U11B-IO_L32P_A17_M1A8_1-PadH12)") (class "Default")
      (node (ref "U11") (pin "H12") (pinfunction "IO_L32P_A17_M1A8_1_H12") (pintype "bidirectional"))
    )
    (net (code "143") (name "unconnected-(U11B-IO_L34N_A12_M1BA2_1-PadK13)") (class "Default")
      (node (ref "U11") (pin "K13") (pinfunction "IO_L34N_A12_M1BA2_1_K13") (pintype "bidirectional"))
    )
    (net (code "144") (name "unconnected-(U11B-IO_L34P_A13_M1WE_1-PadK12)") (class "Default")
      (node (ref "U11") (pin "K12") (pinfunction "IO_L34P_A13_M1WE_1_K12") (pintype "bidirectional"))
    )
    (net (code "145") (name "unconnected-(U11B-IO_L36N_A8_M1BA1_1-PadH14)") (class "Default")
      (node (ref "U11") (pin "H14") (pinfunction "IO_L36N_A8_M1BA1_1_H14") (pintype "bidirectional"))
    )
    (net (code "146") (name "unconnected-(U11B-IO_L36P_A9_M1BA0_1-PadH13)") (class "Default")
      (node (ref "U11") (pin "H13") (pinfunction "IO_L36P_A9_M1BA0_1_H13") (pintype "bidirectional"))
    )
    (net (code "147") (name "unconnected-(U11B-IO_L37N_A6_M1A1_1-PadH16)") (class "Default")
      (node (ref "U11") (pin "H16") (pinfunction "IO_L37N_A6_M1A1_1_H16") (pintype "bidirectional"))
    )
    (net (code "148") (name "unconnected-(U11B-IO_L37P_A7_M1A0_1-PadH15)") (class "Default")
      (node (ref "U11") (pin "H15") (pinfunction "IO_L37P_A7_M1A0_1_H15") (pintype "bidirectional"))
    )
    (net (code "149") (name "unconnected-(U11B-IO_L38N_A4_M1CLKN_1-PadG18)") (class "Default")
      (node (ref "U11") (pin "G18") (pinfunction "IO_L38N_A4_M1CLKN_1_G18") (pintype "bidirectional"))
    )
    (net (code "150") (name "unconnected-(U11B-IO_L38P_A5_M1CLK_1-PadG16)") (class "Default")
      (node (ref "U11") (pin "G16") (pinfunction "IO_L38P_A5_M1CLK_1_G16") (pintype "bidirectional"))
    )
    (net (code "151") (name "unconnected-(U11B-IO_L39N_M1ODT_1-PadK14)") (class "Default")
      (node (ref "U11") (pin "K14") (pinfunction "IO_L39N_M1ODT_1_K14") (pintype "bidirectional"))
    )
    (net (code "152") (name "unconnected-(U11B-IO_L39P_M1A3_1-PadJ13)") (class "Default")
      (node (ref "U11") (pin "J13") (pinfunction "IO_L39P_M1A3_1_J13") (pintype "bidirectional"))
    )
    (net (code "153") (name "unconnected-(U11B-IO_L40N_GCLK10_M1A6_1-PadL13)") (class "Default")
      (node (ref "U11") (pin "L13") (pinfunction "IO_L40N_GCLK10_M1A6_1_L13") (pintype "bidirectional"))
    )
    (net (code "154") (name "unconnected-(U11B-IO_L40P_GCLK11_M1A5_1-PadL12)") (class "Default")
      (node (ref "U11") (pin "L12") (pinfunction "IO_L40P_GCLK11_M1A5_1_L12") (pintype "bidirectional"))
    )
    (net (code "155") (name "unconnected-(U11B-IO_L41N_GCLK8_M1CASN_1-PadK16)") (class "Default")
      (node (ref "U11") (pin "K16") (pinfunction "IO_L41N_GCLK8_M1CASN_1_K16") (pintype "bidirectional"))
    )
    (net (code "156") (name "unconnected-(U11B-IO_L41P_GCLK9_IRDY1_M1RASN_1-PadK15)") (class "Default")
      (node (ref "U11") (pin "K15") (pinfunction "IO_L41P_GCLK9_IRDY1_M1RASN_1_K15") (pintype "bidirectional"))
    )
    (net (code "157") (name "unconnected-(U11B-IO_L42N_GCLK6_TRDY1_M1LDM_1-PadL16)") (class "Default")
      (node (ref "U11") (pin "L16") (pinfunction "IO_L42N_GCLK6_TRDY1_M1LDM_1_L16") (pintype "bidirectional"))
    )
    (net (code "158") (name "unconnected-(U11B-IO_L43N_GCLK4_M1DQ5_1-PadH18)") (class "Default")
      (node (ref "U11") (pin "H18") (pinfunction "IO_L43N_GCLK4_M1DQ5_1_H18") (pintype "bidirectional"))
    )
    (net (code "159") (name "unconnected-(U11B-IO_L44N_A2_M1DQ7_1-PadJ18)") (class "Default")
      (node (ref "U11") (pin "J18") (pinfunction "IO_L44N_A2_M1DQ7_1_J18") (pintype "bidirectional"))
    )
    (net (code "160") (name "unconnected-(U11B-IO_L44P_A3_M1DQ6_1-PadJ16)") (class "Default")
      (node (ref "U11") (pin "J16") (pinfunction "IO_L44P_A3_M1DQ6_1_J16") (pintype "bidirectional"))
    )
    (net (code "161") (name "unconnected-(U11B-IO_L45N_A0_M1LDQSN_1-PadK18)") (class "Default")
      (node (ref "U11") (pin "K18") (pinfunction "IO_L45N_A0_M1LDQSN_1_K18") (pintype "bidirectional"))
    )
    (net (code "162") (name "unconnected-(U11B-IO_L45P_A1_M1LDQS_1-PadK17)") (class "Default")
      (node (ref "U11") (pin "K17") (pinfunction "IO_L45P_A1_M1LDQS_1_K17") (pintype "bidirectional"))
    )
    (net (code "163") (name "unconnected-(U11B-IO_L46N_FOE_B_M1DQ3_1-PadL18)") (class "Default")
      (node (ref "U11") (pin "L18") (pinfunction "IO_L46N_FOE_B_M1DQ3_1_L18") (pintype "bidirectional"))
    )
    (net (code "164") (name "unconnected-(U11B-IO_L46P_FCS_B_M1DQ2_1-PadL17)") (class "Default")
      (node (ref "U11") (pin "L17") (pinfunction "IO_L46P_FCS_B_M1DQ2_1_L17") (pintype "bidirectional"))
    )
    (net (code "165") (name "unconnected-(U11B-IO_L47N_LDC_M1DQ1_1-PadM18)") (class "Default")
      (node (ref "U11") (pin "M18") (pinfunction "IO_L47N_LDC_M1DQ1_1_M18") (pintype "bidirectional"))
    )
    (net (code "166") (name "unconnected-(U11B-IO_L47P_FWE_B_M1DQ0_1-PadM16)") (class "Default")
      (node (ref "U11") (pin "M16") (pinfunction "IO_L47P_FWE_B_M1DQ0_1_M16") (pintype "bidirectional"))
    )
    (net (code "167") (name "unconnected-(U11B-IO_L48P_HDC_M1DQ8_1-PadN17)") (class "Default")
      (node (ref "U11") (pin "N17") (pinfunction "IO_L48P_HDC_M1DQ8_1_N17") (pintype "bidirectional"))
    )
    (net (code "168") (name "unconnected-(U11B-IO_L50P_M1UDQS_1-PadN15)") (class "Default")
      (node (ref "U11") (pin "N15") (pinfunction "IO_L50P_M1UDQS_1_N15") (pintype "bidirectional"))
    )
    (net (code "169") (name "unconnected-(U11B-IO_L53N_VREF_1-PadN14)") (class "Default")
      (node (ref "U11") (pin "N14") (pinfunction "IO_L53N_VREF_1_N14") (pintype "bidirectional"))
    )
    (net (code "170") (name "unconnected-(U11B-IO_L53P_1-PadM14)") (class "Default")
      (node (ref "U11") (pin "M14") (pinfunction "IO_L53P_1_M14") (pintype "bidirectional"))
    )
    (net (code "171") (name "unconnected-(U11B-IO_L61N_1-PadM13)") (class "Default")
      (node (ref "U11") (pin "M13") (pinfunction "IO_L61N_1_M13") (pintype "bidirectional"))
    )
    (net (code "172") (name "unconnected-(U11B-IO_L61P_1-PadL14)") (class "Default")
      (node (ref "U11") (pin "L14") (pinfunction "IO_L61P_1_L14") (pintype "bidirectional"))
    )
    (net (code "173") (name "unconnected-(U11B-IO_L74N_DOUT_BUSY_1-PadP16)") (class "Default")
      (node (ref "U11") (pin "P16") (pinfunction "IO_L74N_DOUT_BUSY_1_P16") (pintype "bidirectional"))
    )
    (net (code "174") (name "unconnected-(U11B-IO_L74P_AWAKE_1-PadP15)") (class "Default")
      (node (ref "U11") (pin "P15") (pinfunction "IO_L74P_AWAKE_1_P15") (pintype "bidirectional"))
    )
    (net (code "175") (name "unconnected-(U11C-IO_L1N_M0_CMPMISO_2-PadT15)") (class "Default")
      (node (ref "U11") (pin "T15") (pinfunction "IO_L1N_M0_CMPMISO_2_T15") (pintype "bidirectional"))
    )
    (net (code "176") (name "unconnected-(U11C-IO_L2N_CMPMOSI_2-PadV16)") (class "Default")
      (node (ref "U11") (pin "V16") (pinfunction "IO_L2N_CMPMOSI_2_V16") (pintype "bidirectional"))
    )
    (net (code "177") (name "unconnected-(U11C-IO_L2P_CMPCLK_2-PadU16)") (class "Default")
      (node (ref "U11") (pin "U16") (pinfunction "IO_L2P_CMPCLK_2_U16") (pintype "bidirectional"))
    )
    (net (code "178") (name "unconnected-(U11C-IO_L3N_MOSI_CSI_B_MISO0_2-PadT13)") (class "Default")
      (node (ref "U11") (pin "T13") (pinfunction "IO_L3N_MOSI_CSI_B_MISO0_2_T13") (pintype "bidirectional"))
    )
    (net (code "179") (name "unconnected-(U11C-IO_L13N_D10_2-PadP12)") (class "Default")
      (node (ref "U11") (pin "P12") (pinfunction "IO_L13N_D10_2_P12") (pintype "bidirectional"))
    )
    (net (code "180") (name "unconnected-(U11C-IO_L13P_M1_2-PadN12)") (class "Default")
      (node (ref "U11") (pin "N12") (pinfunction "IO_L13P_M1_2_N12") (pintype "bidirectional"))
    )
    (net (code "181") (name "unconnected-(U11C-IO_L15N_2-PadN11)") (class "Default")
      (node (ref "U11") (pin "N11") (pinfunction "IO_L15N_2_N11") (pintype "bidirectional"))
    )
    (net (code "182") (name "unconnected-(U11C-IO_L15P_2-PadM11)") (class "Default")
      (node (ref "U11") (pin "M11") (pinfunction "IO_L15P_2_M11") (pintype "bidirectional"))
    )
    (net (code "183") (name "unconnected-(U11C-IO_L16N_VREF_2-PadT11)") (class "Default")
      (node (ref "U11") (pin "T11") (pinfunction "IO_L16N_VREF_2_T11") (pintype "bidirectional"))
    )
    (net (code "184") (name "unconnected-(U11C-IO_L16P_2-PadR11)") (class "Default")
      (node (ref "U11") (pin "R11") (pinfunction "IO_L16P_2_R11") (pintype "bidirectional"))
    )
    (net (code "185") (name "unconnected-(U11C-IO_L19P_2-PadT12)") (class "Default")
      (node (ref "U11") (pin "T12") (pinfunction "IO_L19P_2_T12") (pintype "bidirectional"))
    )
    (net (code "186") (name "unconnected-(U11C-IO_L20N_2-PadP11)") (class "Default")
      (node (ref "U11") (pin "P11") (pinfunction "IO_L20N_2_P11") (pintype "bidirectional"))
    )
    (net (code "187") (name "unconnected-(U11C-IO_L20P_2-PadN10)") (class "Default")
      (node (ref "U11") (pin "N10") (pinfunction "IO_L20P_2_N10") (pintype "bidirectional"))
    )
    (net (code "188") (name "unconnected-(U11C-IO_L22N_2-PadN9)") (class "Default")
      (node (ref "U11") (pin "N9") (pinfunction "IO_L22N_2_N9") (pintype "bidirectional"))
    )
    (net (code "189") (name "unconnected-(U11C-IO_L22P_2-PadM10)") (class "Default")
      (node (ref "U11") (pin "M10") (pinfunction "IO_L22P_2_M10") (pintype "bidirectional"))
    )
    (net (code "190") (name "unconnected-(U11C-IO_L29N_GCLK2_2-PadT10)") (class "Default")
      (node (ref "U11") (pin "T10") (pinfunction "IO_L29N_GCLK2_2_T10") (pintype "bidirectional"))
    )
    (net (code "191") (name "unconnected-(U11C-IO_L31N_GCLK30_D15_2-PadT8)") (class "Default")
      (node (ref "U11") (pin "T8") (pinfunction "IO_L31N_GCLK30_D15_2_T8") (pintype "bidirectional"))
    )
    (net (code "192") (name "unconnected-(U11C-IO_L32N_GCLK28_2-PadV9)") (class "Default")
      (node (ref "U11") (pin "V9") (pinfunction "IO_L32N_GCLK28_2_V9") (pintype "bidirectional"))
    )
    (net (code "193") (name "unconnected-(U11C-IO_L32P_GCLK29_2-PadT9)") (class "Default")
      (node (ref "U11") (pin "T9") (pinfunction "IO_L32P_GCLK29_2_T9") (pintype "bidirectional"))
    )
    (net (code "194") (name "unconnected-(U11C-IO_L40N_2-PadN8)") (class "Default")
      (node (ref "U11") (pin "N8") (pinfunction "IO_L40N_2_N8") (pintype "bidirectional"))
    )
    (net (code "195") (name "unconnected-(U11C-IO_L40P_2-PadM8)") (class "Default")
      (node (ref "U11") (pin "M8") (pinfunction "IO_L40P_2_M8") (pintype "bidirectional"))
    )
    (net (code "196") (name "unconnected-(U11C-IO_L41N_VREF_2-PadV8)") (class "Default")
      (node (ref "U11") (pin "V8") (pinfunction "IO_L41N_VREF_2_V8") (pintype "bidirectional"))
    )
    (net (code "197") (name "unconnected-(U11C-IO_L41P_2-PadU8)") (class "Default")
      (node (ref "U11") (pin "U8") (pinfunction "IO_L41P_2_U8") (pintype "bidirectional"))
    )
    (net (code "198") (name "unconnected-(U11C-IO_L43N_2-PadV7)") (class "Default")
      (node (ref "U11") (pin "V7") (pinfunction "IO_L43N_2_V7") (pintype "bidirectional"))
    )
    (net (code "199") (name "unconnected-(U11C-IO_L43P_2-PadU7)") (class "Default")
      (node (ref "U11") (pin "U7") (pinfunction "IO_L43P_2_U7") (pintype "bidirectional"))
    )
    (net (code "200") (name "unconnected-(U11C-IO_L44N_2-PadP8)") (class "Default")
      (node (ref "U11") (pin "P8") (pinfunction "IO_L44N_2_P8") (pintype "bidirectional"))
    )
    (net (code "201") (name "unconnected-(U11C-IO_L44P_2-PadN7)") (class "Default")
      (node (ref "U11") (pin "N7") (pinfunction "IO_L44P_2_N7") (pintype "bidirectional"))
    )
    (net (code "202") (name "unconnected-(U11C-IO_L46N_2-PadT7)") (class "Default")
      (node (ref "U11") (pin "T7") (pinfunction "IO_L46N_2_T7") (pintype "bidirectional"))
    )
    (net (code "203") (name "unconnected-(U11C-IO_L46P_2-PadR7)") (class "Default")
      (node (ref "U11") (pin "R7") (pinfunction "IO_L46P_2_R7") (pintype "bidirectional"))
    )
    (net (code "204") (name "unconnected-(U11C-IO_L48P_D7_2-PadR5)") (class "Default")
      (node (ref "U11") (pin "R5") (pinfunction "IO_L48P_D7_2_R5") (pintype "bidirectional"))
    )
    (net (code "205") (name "unconnected-(U11C-IO_L62N_D6_2-PadT3)") (class "Default")
      (node (ref "U11") (pin "T3") (pinfunction "IO_L62N_D6_2_T3") (pintype "bidirectional"))
    )
    (net (code "206") (name "unconnected-(U11C-IO_L62P_D5_2-PadR3)") (class "Default")
      (node (ref "U11") (pin "R3") (pinfunction "IO_L62P_D5_2_R3") (pintype "bidirectional"))
    )
    (net (code "207") (name "unconnected-(U11C-IO_L63P_2-PadT4)") (class "Default")
      (node (ref "U11") (pin "T4") (pinfunction "IO_L63P_2_T4") (pintype "bidirectional"))
    )
    (net (code "208") (name "unconnected-(U11C-IO_L64N_D9_2-PadP6)") (class "Default")
      (node (ref "U11") (pin "P6") (pinfunction "IO_L64N_D9_2_P6") (pintype "bidirectional"))
    )
    (net (code "209") (name "unconnected-(U11C-IO_L64P_D8_2-PadN5)") (class "Default")
      (node (ref "U11") (pin "N5") (pinfunction "IO_L64P_D8_2_N5") (pintype "bidirectional"))
    )
    (net (code "210") (name "unconnected-(U11C-IO_L65N_CSO_B_2-PadV3)") (class "Default")
      (node (ref "U11") (pin "V3") (pinfunction "IO_L65N_CSO_B_2_V3") (pintype "bidirectional"))
    )
    (net (code "211") (name "unconnected-(U11D-IO_L1N_VREF_3-PadN3)") (class "Default")
      (node (ref "U11") (pin "N3") (pinfunction "IO_L1N_VREF_3_N3") (pintype "bidirectional"))
    )
    (net (code "212") (name "unconnected-(U11D-IO_L1P_3-PadN4)") (class "Default")
      (node (ref "U11") (pin "N4") (pinfunction "IO_L1P_3_N4") (pintype "bidirectional"))
    )
    (net (code "213") (name "unconnected-(U11D-IO_L2N_3-PadP3)") (class "Default")
      (node (ref "U11") (pin "P3") (pinfunction "IO_L2N_3_P3") (pintype "bidirectional"))
    )
    (net (code "214") (name "unconnected-(U11D-IO_L2P_3-PadP4)") (class "Default")
      (node (ref "U11") (pin "P4") (pinfunction "IO_L2P_3_P4") (pintype "bidirectional"))
    )
    (net (code "215") (name "unconnected-(U11D-IO_L31N_VREF_3-PadM5)") (class "Default")
      (node (ref "U11") (pin "M5") (pinfunction "IO_L31N_VREF_3_M5") (pintype "bidirectional"))
    )
    (net (code "216") (name "unconnected-(U11D-IO_L43N_GCLK22_IRDY2_M3CASN_3-PadK5)") (class "Default")
      (node (ref "U11") (pin "K5") (pinfunction "IO_L43N_GCLK22_IRDY2_M3CASN_3_K5") (pintype "bidirectional"))
    )
    (net (code "217") (name "unconnected-(U11D-IO_L43P_GCLK23_M3RASN_3-PadL5)") (class "Default")
      (node (ref "U11") (pin "L5") (pinfunction "IO_L43P_GCLK23_M3RASN_3_L5") (pintype "bidirectional"))
    )
    (net (code "218") (name "unconnected-(U11D-IO_L44N_GCLK20_M3A6_3-PadH3)") (class "Default")
      (node (ref "U11") (pin "H3") (pinfunction "IO_L44N_GCLK20_M3A6_3_H3") (pintype "bidirectional"))
    )
    (net (code "219") (name "unconnected-(U11D-IO_L44P_GCLK21_M3A5_3-PadH4)") (class "Default")
      (node (ref "U11") (pin "H4") (pinfunction "IO_L44P_GCLK21_M3A5_3_H4") (pintype "bidirectional"))
    )
    (net (code "220") (name "unconnected-(U11D-IO_L45N_M3ODT_3-PadK6)") (class "Default")
      (node (ref "U11") (pin "K6") (pinfunction "IO_L45N_M3ODT_3_K6") (pintype "bidirectional"))
    )
    (net (code "221") (name "unconnected-(U11D-IO_L45P_M3A3_3-PadL7)") (class "Default")
      (node (ref "U11") (pin "L7") (pinfunction "IO_L45P_M3A3_3_L7") (pintype "bidirectional"))
    )
    (net (code "222") (name "unconnected-(U11D-IO_L46P_M3CLK_3-PadG3)") (class "Default")
      (node (ref "U11") (pin "G3") (pinfunction "IO_L46P_M3CLK_3_G3") (pintype "bidirectional"))
    )
    (net (code "223") (name "unconnected-(U11D-IO_L47N_M3A1_3-PadJ6)") (class "Default")
      (node (ref "U11") (pin "J6") (pinfunction "IO_L47N_M3A1_3_J6") (pintype "bidirectional"))
    )
    (net (code "224") (name "unconnected-(U11D-IO_L47P_M3A0_3-PadJ7)") (class "Default")
      (node (ref "U11") (pin "J7") (pinfunction "IO_L47P_M3A0_3_J7") (pintype "bidirectional"))
    )
    (net (code "225") (name "unconnected-(U11D-IO_L49N_M3A2_3-PadH5)") (class "Default")
      (node (ref "U11") (pin "H5") (pinfunction "IO_L49N_M3A2_3_H5") (pintype "bidirectional"))
    )
    (net (code "226") (name "unconnected-(U11D-IO_L49P_M3A7_3-PadH6)") (class "Default")
      (node (ref "U11") (pin "H6") (pinfunction "IO_L49P_M3A7_3_H6") (pintype "bidirectional"))
    )
    (net (code "227") (name "unconnected-(U11D-IO_L50P_M3WE_3-PadE3)") (class "Default")
      (node (ref "U11") (pin "E3") (pinfunction "IO_L50P_M3WE_3_E3") (pintype "bidirectional"))
    )
    (net (code "228") (name "unconnected-(U11D-IO_L51P_M3A10_3-PadF4)") (class "Default")
      (node (ref "U11") (pin "F4") (pinfunction "IO_L51P_M3A10_3_F4") (pintype "bidirectional"))
    )
    (net (code "229") (name "unconnected-(U11D-IO_L53N_M3A12_3-PadG6)") (class "Default")
      (node (ref "U11") (pin "G6") (pinfunction "IO_L53N_M3A12_3_G6") (pintype "bidirectional"))
    )
    (net (code "230") (name "unconnected-(U11D-IO_L53P_M3CKE_3-PadH7)") (class "Default")
      (node (ref "U11") (pin "H7") (pinfunction "IO_L53P_M3CKE_3_H7") (pintype "bidirectional"))
    )
    (net (code "231") (name "unconnected-(U11D-IO_L54P_M3RESET_3-PadE4)") (class "Default")
      (node (ref "U11") (pin "E4") (pinfunction "IO_L54P_M3RESET_3_E4") (pintype "bidirectional"))
    )
    (net (code "232") (name "unconnected-(U11D-IO_L55N_M3A14_3-PadF5)") (class "Default")
      (node (ref "U11") (pin "F5") (pinfunction "IO_L55N_M3A14_3_F5") (pintype "bidirectional"))
    )
    (net (code "233") (name "unconnected-(U11D-IO_L55P_M3A13_3-PadF6)") (class "Default")
      (node (ref "U11") (pin "F6") (pinfunction "IO_L55P_M3A13_3_F6") (pintype "bidirectional"))
    )
    (net (code "234") (name "unconnected-(U11E-CMPCS_B_2-PadP13)") (class "Default")
      (node (ref "U11") (pin "P13") (pinfunction "CMPCS_B_2_P13") (pintype "input+no_connect"))
    )
    (net (code "235") (name "unconnected-(U12-BUSY-PadC1)") (class "Default")
      (node (ref "U12") (pin "C1") (pinfunction "BUSY_C1") (pintype "input+no_connect"))
    )
    (net (code "236") (name "unconnected-(U12-CLKOUT-PadC2)") (class "Default")
      (node (ref "U12") (pin "C2") (pinfunction "CLKOUT_C2") (pintype "output+no_connect"))
    )
    (net (code "237") (name "unconnected-(U12-D1-PadH5)") (class "Default")
      (node (ref "U12") (pin "H5") (pinfunction "D1_H5") (pintype "tri_state+no_connect"))
    )
    (net (code "238") (name "unconnected-(U12-D2-PadE5)") (class "Default")
      (node (ref "U12") (pin "E5") (pinfunction "D2_E5") (pintype "tri_state+no_connect"))
    )
    (net (code "239") (name "unconnected-(U12-D3-PadD5)") (class "Default")
      (node (ref "U12") (pin "D5") (pinfunction "D3_D5") (pintype "tri_state+no_connect"))
    )
    (net (code "240") (name "unconnected-(U12-D4-PadC5)") (class "Default")
      (node (ref "U12") (pin "C5") (pinfunction "D4_C5") (pintype "tri_state+no_connect"))
    )
    (net (code "241") (name "unconnected-(U12-D5-PadB5)") (class "Default")
      (node (ref "U12") (pin "B5") (pinfunction "D5_B5") (pintype "tri_state+no_connect"))
    )
    (net (code "242") (name "unconnected-(U12-D6-PadA5)") (class "Default")
      (node (ref "U12") (pin "A5") (pinfunction "D6_A5") (pintype "tri_state+no_connect"))
    )
    (net (code "243") (name "unconnected-(U12-D7-PadA6)") (class "Default")
      (node (ref "U12") (pin "A6") (pinfunction "D7_A6") (pintype "tri_state+no_connect"))
    )
    (net (code "244") (name "unconnected-(U12-DNC-PadA4)") (class "Default")
      (node (ref "U12") (pin "A4") (pinfunction "DNC_A4") (pintype "passive+no_connect"))
    )
    (net (code "245") (name "unconnected-(U12-DNC-PadC3)") (class "Default")
      (node (ref "U12") (pin "C3") (pinfunction "DNC_C3") (pintype "passive+no_connect"))
    )
    (net (code "246") (name "unconnected-(U12-DNC-PadC4)") (class "Default")
      (node (ref "U12") (pin "C4") (pinfunction "DNC_C4") (pintype "passive+no_connect"))
    )
    (net (code "247") (name "unconnected-(U12-DNC-PadD3)") (class "Default")
      (node (ref "U12") (pin "D3") (pinfunction "DNC_D3") (pintype "passive+no_connect"))
    )
    (net (code "248") (name "unconnected-(U12-DNC-PadD4)") (class "Default")
      (node (ref "U12") (pin "D4") (pinfunction "DNC_D4") (pintype "passive+no_connect"))
    )
    (net (code "249") (name "unconnected-(U12-DNC-PadE3)") (class "Default")
      (node (ref "U12") (pin "E3") (pinfunction "DNC_E3") (pintype "passive+no_connect"))
    )
    (net (code "250") (name "unconnected-(U12-DNC-PadE4)") (class "Default")
      (node (ref "U12") (pin "E4") (pinfunction "DNC_E4") (pintype "passive+no_connect"))
    )
    (net (code "251") (name "unconnected-(U12-DNC-PadF2)") (class "Default")
      (node (ref "U12") (pin "F2") (pinfunction "DNC_F2") (pintype "passive+no_connect"))
    )
    (net (code "252") (name "unconnected-(U12-DNC-PadF3)") (class "Default")
      (node (ref "U12") (pin "F3") (pinfunction "DNC_F3") (pintype "passive+no_connect"))
    )
    (net (code "253") (name "unconnected-(U12-DNC-PadF4)") (class "Default")
      (node (ref "U12") (pin "F4") (pinfunction "DNC_F4") (pintype "passive+no_connect"))
    )
    (net (code "254") (name "unconnected-(U12-DNC-PadG2)") (class "Default")
      (node (ref "U12") (pin "G2") (pinfunction "DNC_G2") (pintype "passive+no_connect"))
    )
    (net (code "255") (name "unconnected-(U12-~{CEO}-PadD2)") (class "Default")
      (node (ref "U12") (pin "D2") (pinfunction "~{CEO}_D2") (pintype "output+no_connect"))
    )
  )
)
